# crawler2head.net
KiCad netlist of a schematic drawn in EAGLE
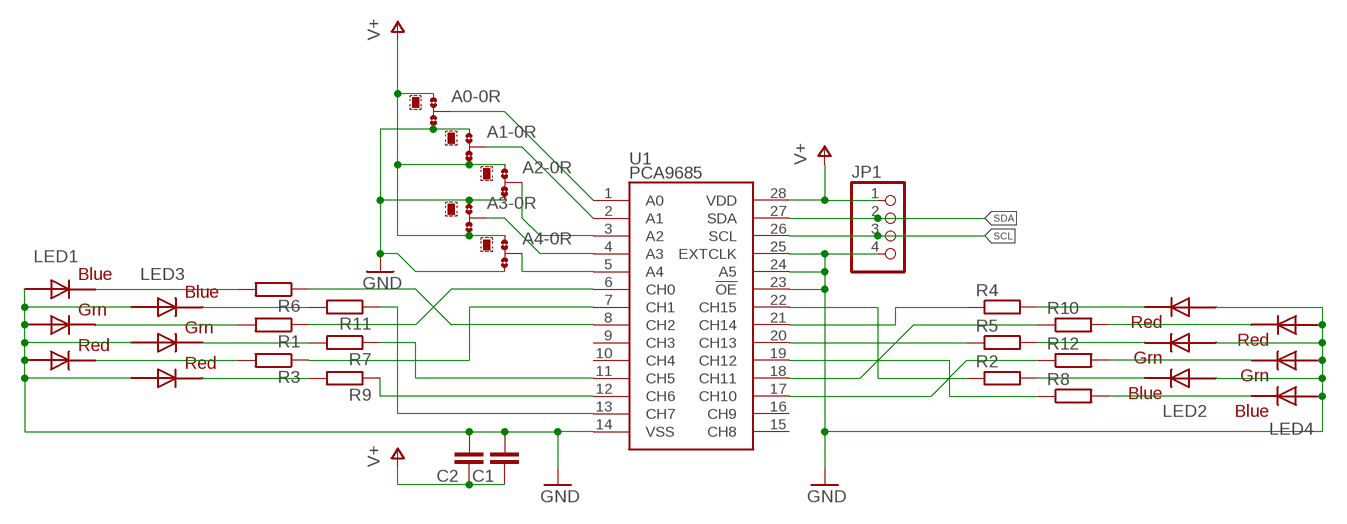
[diagram p0: schematic, sheet 1]

(export (version "E")
  (design (tool "Eeschema 10.0.6"))
  (components
    (comp (ref "A0")
      (value "A0")
      (footprint "eagle-import:B0R-JMP")
      (libsource (lib "eagle-import") (part "0R-JUMPB"))
    )
    (comp (ref "A1")
      (value "0R-JUMPB")
      (footprint "eagle-import:B0R-JMP")
      (libsource (lib "eagle-import") (part "0R-JUMPB"))
    )
    (comp (ref "A2")
      (value "0R-JUMPB")
      (footprint "eagle-import:B0R-JMP")
      (libsource (lib "eagle-import") (part "0R-JUMPB"))
    )
    (comp (ref "A3")
      (value "0R-JUMPB")
      (footprint "eagle-import:B0R-JMP")
      (libsource (lib "eagle-import") (part "0R-JUMPB"))
    )
    (comp (ref "A4")
      (value "0R-JUMPB")
      (footprint "eagle-import:B0R-JMP")
      (libsource (lib "eagle-import") (part "0R-JUMPB"))
    )
    (comp (ref "C1")
      (value "C-EUC3216")
      (footprint "eagle-import:C3216")
      (libsource (lib "eagle-import") (part "C-EUC3216"))
    )
    (comp (ref "C2")
      (value "C-EUC0603")
      (footprint "eagle-import:C0603")
      (libsource (lib "eagle-import") (part "C-EUC0603"))
    )
    (comp (ref "JP1")
      (value "PINHD-1X4/90")
      (footprint "eagle-import:1X04_90")
      (libsource (lib "eagle-import") (part "PINHD-1X4/90"))
    )
    (comp (ref "LED1")
      (value "RGBLED5050")
      (footprint "eagle-import:RGBLED5050")
      (libsource (lib "eagle-import") (part "RGBLED5050"))
    )
    (comp (ref "LED2")
      (value "RGBLED5050")
      (footprint "eagle-import:RGBLED5050")
      (libsource (lib "eagle-import") (part "RGBLED5050"))
    )
    (comp (ref "LED3")
      (value "RGBLED5050")
      (footprint "eagle-import:RGBLED5050")
      (libsource (lib "eagle-import") (part "RGBLED5050"))
    )
    (comp (ref "LED4")
      (value "RGBLED5050")
      (footprint "eagle-import:RGBLED5050")
      (libsource (lib "eagle-import") (part "RGBLED5050"))
    )
    (comp (ref "R1")
      (value "R-EU_R0603")
      (footprint "eagle-import:R0603")
      (libsource (lib "eagle-import") (part "R-EU_R0603"))
    )
    (comp (ref "R2")
      (value "R-EU_R0603")
      (footprint "eagle-import:R0603")
      (libsource (lib "eagle-import") (part "R-EU_R0603"))
    )
    (comp (ref "R3")
      (value "R-EU_R0603")
      (footprint "eagle-import:R0603")
      (libsource (lib "eagle-import") (part "R-EU_R0603"))
    )
    (comp (ref "R4")
      (value "R-EU_R0603")
      (footprint "eagle-import:R0603")
      (libsource (lib "eagle-import") (part "R-EU_R0603"))
    )
    (comp (ref "R5")
      (value "R-EU_R0603")
      (footprint "eagle-import:R0603")
      (libsource (lib "eagle-import") (part "R-EU_R0603"))
    )
    (comp (ref "R6")
      (value "R-EU_R0603")
      (footprint "eagle-import:R0603")
      (libsource (lib "eagle-import") (part "R-EU_R0603"))
    )
    (comp (ref "R7")
      (value "R-EU_R0603")
      (footprint "eagle-import:R0603")
      (libsource (lib "eagle-import") (part "R-EU_R0603"))
    )
    (comp (ref "R8")
      (value "R-EU_R0603")
      (footprint "eagle-import:R0603")
      (libsource (lib "eagle-import") (part "R-EU_R0603"))
    )
    (comp (ref "R9")
      (value "R-EU_R0603")
      (footprint "eagle-import:R0603")
      (libsource (lib "eagle-import") (part "R-EU_R0603"))
    )
    (comp (ref "R10")
      (value "R-EU_R0603")
      (footprint "eagle-import:R0603")
      (libsource (lib "eagle-import") (part "R-EU_R0603"))
    )
    (comp (ref "R11")
      (value "R-EU_R0603")
      (footprint "eagle-import:R0603")
      (libsource (lib "eagle-import") (part "R-EU_R0603"))
    )
    (comp (ref "R12")
      (value "R-EU_R0603")
      (footprint "eagle-import:R0603")
      (libsource (lib "eagle-import") (part "R-EU_R0603"))
    )
    (comp (ref "U1")
      (value "PCA9685")
      (footprint "eagle-import:TSSOP-28_4MM")
      (libsource (lib "eagle-import") (part "PCA9685"))
    )
  )
  (nets
    (net (code "1") (name "GND") (class "Default")
      (node (ref "A0") (pin "3") (pinfunction "3_3") (pintype "passive"))
      (node (ref "A1") (pin "1") (pinfunction "1_1") (pintype "passive"))
      (node (ref "A2") (pin "3") (pinfunction "3_3") (pintype "passive"))
      (node (ref "A3") (pin "1") (pinfunction "1_1") (pintype "passive"))
      (node (ref "A4") (pin "3") (pinfunction "3_3") (pintype "passive"))
      (node (ref "C1") (pin "2") (pinfunction "2_2") (pintype "passive"))
      (node (ref "C2") (pin "2") (pinfunction "2_2") (pintype "passive"))
      (node (ref "JP1") (pin "4") (pinfunction "4_4") (pintype "passive"))
      (node (ref "LED1") (pin "1") (pinfunction "GREEN_A_1") (pintype "bidirectional"))
      (node (ref "LED1") (pin "2") (pinfunction "RED_A_2") (pintype "bidirectional"))
      (node (ref "LED1") (pin "3") (pinfunction "BLUE_A_3") (pintype "bidirectional"))
      (node (ref "LED2") (pin "1") (pinfunction "GREEN_A_1") (pintype "bidirectional"))
      (node (ref "LED2") (pin "2") (pinfunction "RED_A_2") (pintype "bidirectional"))
      (node (ref "LED2") (pin "3") (pinfunction "BLUE_A_3") (pintype "bidirectional"))
      (node (ref "LED3") (pin "1") (pinfunction "GREEN_A_1") (pintype "bidirectional"))
      (node (ref "LED3") (pin "2") (pinfunction "RED_A_2") (pintype "bidirectional"))
      (node (ref "LED3") (pin "3") (pinfunction "BLUE_A_3") (pintype "bidirectional"))
      (node (ref "LED4") (pin "1") (pinfunction "GREEN_A_1") (pintype "bidirectional"))
      (node (ref "LED4") (pin "2") (pinfunction "RED_A_2") (pintype "bidirectional"))
      (node (ref "LED4") (pin "3") (pinfunction "BLUE_A_3") (pintype "bidirectional"))
      (node (ref "U1") (pin "14") (pinfunction "VSS_14") (pintype "bidirectional"))
      (node (ref "U1") (pin "23") (pinfunction "~{OE}_23") (pintype "bidirectional"))
      (node (ref "U1") (pin "24") (pinfunction "A5_24") (pintype "bidirectional"))
      (node (ref "U1") (pin "25") (pinfunction "EXTCLK_25") (pintype "bidirectional"))
    )
    (net (code "2") (name "Net-(LED1-BLUE_C)") (class "Default")
      (node (ref "LED1") (pin "4") (pinfunction "BLUE_C_4") (pintype "bidirectional"))
      (node (ref "R6") (pin "2") (pinfunction "2_2") (pintype "passive"))
    )
    (net (code "3") (name "Net-(LED1-GREEN_C)") (class "Default")
      (node (ref "LED1") (pin "6") (pinfunction "GREEN_C_6") (pintype "bidirectional"))
      (node (ref "R1") (pin "2") (pinfunction "2_2") (pintype "passive"))
    )
    (net (code "4") (name "Net-(LED1-RED_C)") (class "Default")
      (node (ref "LED1") (pin "5") (pinfunction "RED_C_5") (pintype "bidirectional"))
      (node (ref "R3") (pin "2") (pinfunction "2_2") (pintype "passive"))
    )
    (net (code "5") (name "Net-(LED2-BLUE_C)") (class "Default")
      (node (ref "LED2") (pin "4") (pinfunction "BLUE_C_4") (pintype "bidirectional"))
      (node (ref "R2") (pin "2") (pinfunction "2_2") (pintype "passive"))
    )
    (net (code "6") (name "Net-(LED2-GREEN_C)") (class "Default")
      (node (ref "LED2") (pin "6") (pinfunction "GREEN_C_6") (pintype "bidirectional"))
      (node (ref "R5") (pin "2") (pinfunction "2_2") (pintype "passive"))
    )
    (net (code "7") (name "Net-(LED2-RED_C)") (class "Default")
      (node (ref "LED2") (pin "5") (pinfunction "RED_C_5") (pintype "bidirectional"))
      (node (ref "R4") (pin "2") (pinfunction "2_2") (pintype "passive"))
    )
    (net (code "8") (name "Net-(LED3-BLUE_C)") (class "Default")
      (node (ref "LED3") (pin "4") (pinfunction "BLUE_C_4") (pintype "bidirectional"))
      (node (ref "R11") (pin "2") (pinfunction "2_2") (pintype "passive"))
    )
    (net (code "9") (name "Net-(LED3-GREEN_C)") (class "Default")
      (node (ref "LED3") (pin "6") (pinfunction "GREEN_C_6") (pintype "bidirectional"))
      (node (ref "R7") (pin "2") (pinfunction "2_2") (pintype "passive"))
    )
    (net (code "10") (name "Net-(LED3-RED_C)") (class "Default")
      (node (ref "LED3") (pin "5") (pinfunction "RED_C_5") (pintype "bidirectional"))
      (node (ref "R9") (pin "2") (pinfunction "2_2") (pintype "passive"))
    )
    (net (code "11") (name "Net-(LED4-BLUE_C)") (class "Default")
      (node (ref "LED4") (pin "4") (pinfunction "BLUE_C_4") (pintype "bidirectional"))
      (node (ref "R8") (pin "2") (pinfunction "2_2") (pintype "passive"))
    )
    (net (code "12") (name "Net-(LED4-GREEN_C)") (class "Default")
      (node (ref "LED4") (pin "6") (pinfunction "GREEN_C_6") (pintype "bidirectional"))
      (node (ref "R12") (pin "2") (pinfunction "2_2") (pintype "passive"))
    )
    (net (code "13") (name "Net-(LED4-RED_C)") (class "Default")
      (node (ref "LED4") (pin "5") (pinfunction "RED_C_5") (pintype "bidirectional"))
      (node (ref "R10") (pin "2") (pinfunction "2_2") (pintype "passive"))
    )
    (net (code "14") (name "Net-(U1-A0)") (class "Default")
      (node (ref "A0") (pin "2") (pinfunction "2_2") (pintype "passive"))
      (node (ref "U1") (pin "1") (pinfunction "A0_1") (pintype "bidirectional"))
    )
    (net (code "15") (name "Net-(U1-A1)") (class "Default")
      (node (ref "A1") (pin "2") (pinfunction "2_2") (pintype "passive"))
      (node (ref "U1") (pin "2") (pinfunction "A1_2") (pintype "bidirectional"))
    )
    (net (code "16") (name "Net-(U1-A2)") (class "Default")
      (node (ref "A2") (pin "2") (pinfunction "2_2") (pintype "passive"))
      (node (ref "U1") (pin "3") (pinfunction "A2_3") (pintype "bidirectional"))
    )
    (net (code "17") (name "Net-(U1-A3)") (class "Default")
      (node (ref "A3") (pin "2") (pinfunction "2_2") (pintype "passive"))
      (node (ref "U1") (pin "4") (pinfunction "A3_4") (pintype "bidirectional"))
    )
    (net (code "18") (name "Net-(U1-A4)") (class "Default")
      (node (ref "A4") (pin "2") (pinfunction "2_2") (pintype "passive"))
      (node (ref "U1") (pin "5") (pinfunction "A4_5") (pintype "bidirectional"))
    )
    (net (code "19") (name "Net-(U1-CH0)") (class "Default")
      (node (ref "R1") (pin "1") (pinfunction "1_1") (pintype "passive"))
      (node (ref "U1") (pin "6") (pinfunction "CH0_6") (pintype "bidirectional"))
    )
    (net (code "20") (name "Net-(U1-CH1)") (class "Default")
      (node (ref "R3") (pin "1") (pinfunction "1_1") (pintype "passive"))
      (node (ref "U1") (pin "7") (pinfunction "CH1_7") (pintype "bidirectional"))
    )
    (net (code "21") (name "Net-(U1-CH2)") (class "Default")
      (node (ref "R6") (pin "1") (pinfunction "1_1") (pintype "passive"))
      (node (ref "U1") (pin "8") (pinfunction "CH2_8") (pintype "bidirectional"))
    )
    (net (code "22") (name "Net-(U1-CH5)") (class "Default")
      (node (ref "R7") (pin "1") (pinfunction "1_1") (pintype "passive"))
      (node (ref "U1") (pin "11") (pinfunction "CH5_11") (pintype "bidirectional"))
    )
    (net (code "23") (name "Net-(U1-CH6)") (class "Default")
      (node (ref "R9") (pin "1") (pinfunction "1_1") (pintype "passive"))
      (node (ref "U1") (pin "12") (pinfunction "CH6_12") (pintype "bidirectional"))
    )
    (net (code "24") (name "Net-(U1-CH7)") (class "Default")
      (node (ref "R11") (pin "1") (pinfunction "1_1") (pintype "passive"))
      (node (ref "U1") (pin "13") (pinfunction "CH7_13") (pintype "bidirectional"))
    )
    (net (code "25") (name "Net-(U1-CH10)") (class "Default")
      (node (ref "R12") (pin "1") (pinfunction "1_1") (pintype "passive"))
      (node (ref "U1") (pin "17") (pinfunction "CH10_17") (pintype "bidirectional"))
    )
    (net (code "26") (name "Net-(U1-CH11)") (class "Default")
      (node (ref "R10") (pin "1") (pinfunction "1_1") (pintype "passive"))
      (node (ref "U1") (pin "18") (pinfunction "CH11_18") (pintype "bidirectional"))
    )
    (net (code "27") (name "Net-(U1-CH12)") (class "Default")
      (node (ref "R8") (pin "1") (pinfunction "1_1") (pintype "passive"))
      (node (ref "U1") (pin "19") (pinfunction "CH12_19") (pintype "bidirectional"))
    )
    (net (code "28") (name "Net-(U1-CH13)") (class "Default")
      (node (ref "R5") (pin "1") (pinfunction "1_1") (pintype "passive"))
      (node (ref "U1") (pin "20") (pinfunction "CH13_20") (pintype "bidirectional"))
    )
    (net (code "29") (name "Net-(U1-CH14)") (class "Default")
      (node (ref "R4") (pin "1") (pinfunction "1_1") (pintype "passive"))
      (node (ref "U1") (pin "21") (pinfunction "CH14_21") (pintype "bidirectional"))
    )
    (net (code "30") (name "Net-(U1-CH15)") (class "Default")
      (node (ref "R2") (pin "1") (pinfunction "1_1") (pintype "passive"))
      (node (ref "U1") (pin "22") (pinfunction "CH15_22") (pintype "bidirectional"))
    )
    (net (code "31") (name "SCL") (class "Default")
      (node (ref "JP1") (pin "3") (pinfunction "3_3") (pintype "passive"))
      (node (ref "U1") (pin "26") (pinfunction "SCL_26") (pintype "bidirectional"))
    )
    (net (code "32") (name "SDA") (class "Default")
      (node (ref "JP1") (pin "2") (pinfunction "2_2") (pintype "passive"))
      (node (ref "U1") (pin "27") (pinfunction "SDA_27") (pintype "bidirectional"))
    )
    (net (code "33") (name "V+") (class "Default")
      (node (ref "A0") (pin "1") (pinfunction "1_1") (pintype "passive"))
      (node (ref "A1") (pin "3") (pinfunction "3_3") (pintype "passive"))
      (node (ref "A2") (pin "1") (pinfunction "1_1") (pintype "passive"))
      (node (ref "A3") (pin "3") (pinfunction "3_3") (pintype "passive"))
      (node (ref "A4") (pin "1") (pinfunction "1_1") (pintype "passive"))
      (node (ref "C1") (pin "1") (pinfunction "1_1") (pintype "passive"))
      (node (ref "C2") (pin "1") (pinfunction "1_1") (pintype "passive"))
      (node (ref "JP1") (pin "1") (pinfunction "1_1") (pintype "passive"))
      (node (ref "U1") (pin "28") (pinfunction "VDD_28") (pintype "bidirectional"))
    )
    (net (code "34") (name "unconnected-(U1-CH3-Pad9)") (class "Default")
      (node (ref "U1") (pin "9") (pinfunction "CH3_9") (pintype "bidirectional"))
    )
    (net (code "35") (name "unconnected-(U1-CH4-Pad10)") (class "Default")
      (node (ref "U1") (pin "10") (pinfunction "CH4_10") (pintype "bidirectional"))
    )
    (net (code "36") (name "unconnected-(U1-CH8-Pad15)") (class "Default")
      (node (ref "U1") (pin "15") (pinfunction "CH8_15") (pintype "bidirectional"))
    )
    (net (code "37") (name "unconnected-(U1-CH9-Pad16)") (class "Default")
      (node (ref "U1") (pin "16") (pinfunction "CH9_16") (pintype "bidirectional"))
    )
  )
)
